# deepshark_servo.net
KiCad netlist of a schematic drawn in Altium Designer
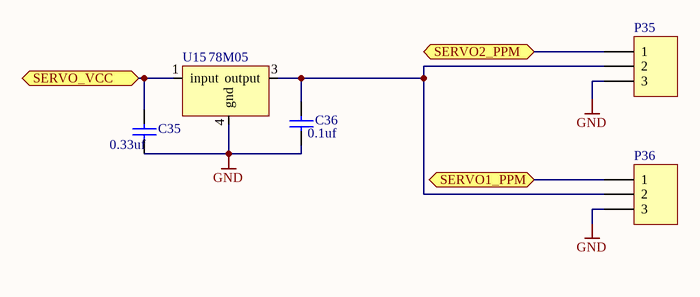
[diagram p0: deepshark_servo.SchDoc]

(export (version "E")
  (design (tool "Eeschema 10.0.6"))
  (components
    (comp (ref "C35")
      (value "0.33uf")
      (footprint "C1206")
      (description "Capacitor (Semiconductor SIM Model)")
      (fields (field (name "Comment") "Cap Semi") (field (name "PUBLISHER") "Altium Limited"))
      (libsource (lib "Miscellaneous Devices") (part "Cap Semi"))
    )
    (comp (ref "C36")
      (value "0.1uf")
      (footprint "6-0805_M")
      (description "Capacitor (Semiconductor SIM Model)")
      (fields (field (name "Comment") "Cap Semi") (field (name "PUBLISHER") "Altium Limited"))
      (libsource (lib "Miscellaneous Devices") (part "Cap Semi"))
    )
    (comp (ref "P35")
      (value "Header 3")
      (footprint "HDR1X3")
      (description "Header, 3-Pin")
      (fields (field (name "PUBLISHER") "Altium Limited"))
      (libsource (lib "Miscellaneous Connectors") (part "Header 3"))
    )
    (comp (ref "P36")
      (value "Header 3")
      (footprint "HDR1X3")
      (description "Header, 3-Pin")
      (fields (field (name "PUBLISHER") "Altium Limited"))
      (libsource (lib "Miscellaneous Connectors") (part "Header 3"))
    )
    (comp (ref "U15")
      (value "78M05")
      (footprint "TO-252AA")
      (libsource (lib "deepshark_sch_lib") (part "78M05"))
    )
  )
  (nets
    (net (code "1") (name "/SERVO1_PPM") (class "Default")
      (node (ref "P36") (pin "1") (pinfunction "1_1") (pintype "passive"))
    )
    (net (code "2") (name "/SERVO2_PPM") (class "Default")
      (node (ref "P35") (pin "1") (pinfunction "1_1") (pintype "passive"))
    )
    (net (code "3") (name "/SERVO_VCC") (class "Default")
      (node (ref "C35") (pin "2") (pinfunction "2_2") (pintype "passive"))
      (node (ref "U15") (pin "1") (pinfunction "input_1") (pintype "passive"))
    )
    (net (code "4") (name "GND") (class "Default")
      (node (ref "C35") (pin "1") (pinfunction "1_1") (pintype "passive"))
      (node (ref "C36") (pin "1") (pinfunction "1_1") (pintype "passive"))
      (node (ref "P35") (pin "3") (pinfunction "3_3") (pintype "passive"))
      (node (ref "P36") (pin "3") (pinfunction "3_3") (pintype "passive"))
      (node (ref "U15") (pin "4") (pinfunction "gnd_4") (pintype "passive"))
    )
    (net (code "5") (name "Net-(U15-output)") (class "Default")
      (node (ref "C36") (pin "2") (pinfunction "2_2") (pintype "passive"))
      (node (ref "P35") (pin "2") (pinfunction "2_2") (pintype "passive"))
      (node (ref "P36") (pin "2") (pinfunction "2_2") (pintype "passive"))
      (node (ref "U15") (pin "3") (pinfunction "output_3") (pintype "passive"))
    )
  )
)
